# Power.net
KiCad netlist of a schematic drawn in Altium Designer
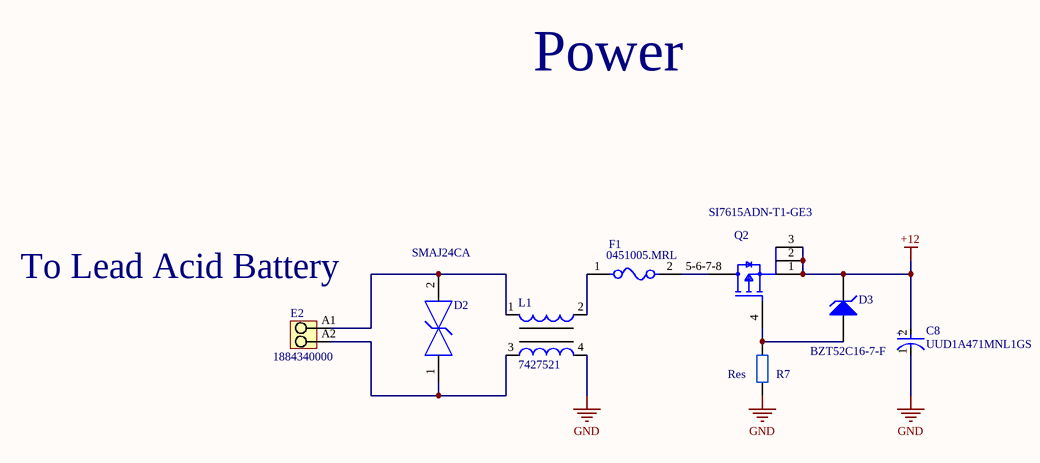
[diagram p0: Power.SchDoc]

(export (version "E")
  (design (tool "Eeschema 10.0.6"))
  (components
    (comp (ref "C8")
      (value "UUD1A471MNL1GS")
      (footprint "FP-UUD1A471MNL1GS-MFG")
      (description "CAP ALUM 470UF 20% 10V SMD")
      (fields (field (name "TOLERANCE") "20%") (field (name "VOLTAGE") "10V"))
      (libsource (lib "Altium Content Vault") (part "203bc49f2ac43e59fd269a8c329ed05"))
    )
    (comp (ref "D2")
      (value "SMAJ24CA")
      (footprint "FP-SMAJ-CA-MFG")
      (description "TVS DIODE 24V 38.9V DO214AC")
      (fields
        (field (name "MANUFACTURER") "Littelfuse")
        (field (name "OCTOPART") "https://octopart.com/smaj24ca-littelfuse-350011")
      )
      (libsource (lib "Altium Content Vault") (part "876f4347bf90aa6f500f43e3cd03972"))
    )
    (comp (ref "D3")
      (value "BZT52C16-7-F")
      (footprint "DIOD-SOD123-2_V")
      (description "Surface Mount Zener Diode, 16 V, -65 to 125 degC, SOD123, RoHS, Tape and Reel")
      (fields (field (name "MANUFACTURER") "Diodes Inc"))
      (libsource (lib "Altium Content Vault") (part "DIOD-DZEN-A1K2-2"))
    )
    (comp (ref "E2")
      (value "1884340000")
      (footprint "LSF_SMT_5_00_135_02")
      (description "OMNIMATE Signal - series LSF")
      (fields (field (name "MANUFACTURER") "Weidmueller"))
      (libsource (lib "Altium Content Vault") (part "Terminal_02_1x02"))
    )
    (comp (ref "F1")
      (value "0451005.MRL")
      (footprint "FP-0451-MFG")
      (description "FUSE BRD MNT 5A 125VAC/VDC 2SMD")
      (fields
        (field (name "OCTOPART") "https://octopart.com/0451005.mrl-littelfuse-566389")
        (field (name "MANUFACTURER") "Littelfuse Inc")
      )
      (libsource (lib "Altium Content Vault") (part "5bcf9b9f640e542cf0359d10258e979"))
    )
    (comp (ref "L1")
      (value "7427521")
      (footprint "WE-CMS")
      (description "Common Mode SMD Bead WE-CMS, Z = 52 Ohm")
      (libsource (lib "Altium Content Vault") (part "PAS-IND-INDUCTOR-4"))
    )
    (comp (ref "Q2")
      (value "SI7615ADN-T1-GE3")
      (footprint "FP-S16-2667_SINGLE-MFG")
      (description "MOSFET P-CH 20V 35A 1212-8S")
      (fields
        (field (name "OCTOPART") "https://octopart.com/si7615adn-t1-ge3-vishay-45331111")
        (field (name "MANUFACTURER") "Vishay")
      )
      (libsource (lib "Altium Content Vault") (part "2fcdebc9db46997103ded74af620a28"))
    )
    (comp (ref "R7")
      (value "Res")
      (footprint "R0603 (1608)")
      (libsource (lib "Moto Symbol Lib") (part "Resistor EU"))
    )
  )
  (nets
    (net (code "1") (name "+12") (class "Default")
      (node (ref "C8") (pin "2") (pinfunction "A_2") (pintype "passive"))
      (node (ref "D3") (pin "2") (pinfunction "K_2") (pintype "passive"))
      (node (ref "Q2") (pin "1") (pinfunction "S_1") (pintype "passive"))
      (node (ref "Q2") (pin "2") (pinfunction "S_2") (pintype "passive"))
      (node (ref "Q2") (pin "3") (pinfunction "S_3") (pintype "passive"))
    )
    (net (code "2") (name "GND") (class "Default")
      (node (ref "C8") (pin "1") (pinfunction "C_1") (pintype "passive"))
      (node (ref "L1") (pin "4") (pinfunction "4_4") (pintype "passive"))
      (node (ref "R7") (pin "1") (pinfunction "1_1") (pintype "power_in"))
    )
    (net (code "3") (name "Net-(D2-Pad1)") (class "Default")
      (node (ref "D2") (pin "1") (pinfunction "1_1") (pintype "passive"))
      (node (ref "E2") (pin "A2") (pinfunction "A2_A2") (pintype "passive"))
      (node (ref "L1") (pin "3") (pinfunction "3_3") (pintype "passive"))
    )
    (net (code "4") (name "Net-(D2-Pad2)") (class "Default")
      (node (ref "D2") (pin "2") (pinfunction "2_2") (pintype "passive"))
      (node (ref "E2") (pin "A1") (pinfunction "A1_A1") (pintype "passive"))
      (node (ref "L1") (pin "1") (pinfunction "1_1") (pintype "passive"))
    )
    (net (code "5") (name "Net-(D3-A)") (class "Default")
      (node (ref "D3") (pin "1") (pinfunction "A_1") (pintype "passive"))
      (node (ref "Q2") (pin "4") (pinfunction "G_4") (pintype "passive"))
      (node (ref "R7") (pin "2") (pinfunction "2_2") (pintype "power_in"))
    )
    (net (code "6") (name "Net-(F1-Pad1)") (class "Default")
      (node (ref "F1") (pin "1") (pinfunction "1_1") (pintype "passive"))
      (node (ref "L1") (pin "2") (pinfunction "2_2") (pintype "passive"))
    )
    (net (code "7") (name "Net-(Q2-D)") (class "Default")
      (node (ref "F1") (pin "2") (pinfunction "2_2") (pintype "passive"))
      (node (ref "Q2") (pin "5-6-7-8") (pinfunction "D_5-6-7-8") (pintype "passive"))
    )
  )
)
